# Power_VCC1V5.net
KiCad netlist of a schematic drawn in Altium Designer
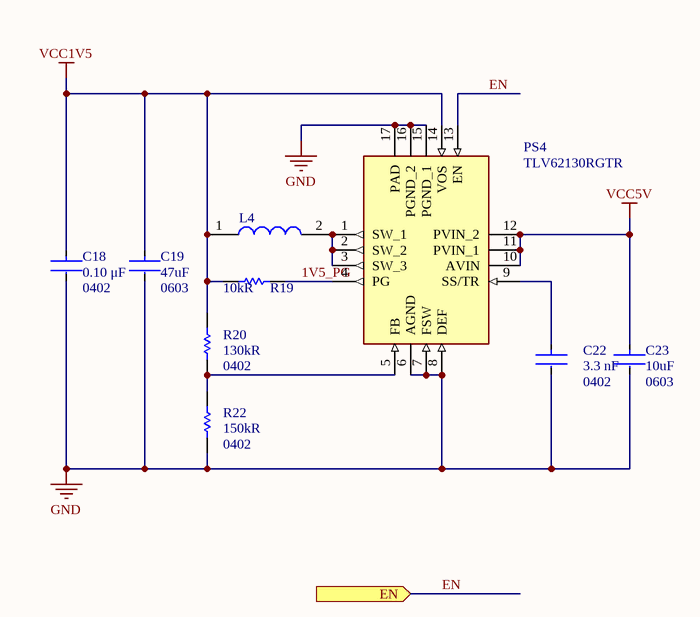
[diagram p0: Power_VCC1V5.SchDoc]

(export (version "E")
  (design (tool "Eeschema 10.0.6"))
  (components
    (comp (ref "C18")
      (value "0.10 μF")
      (footprint "FP-C0402-BB-MFG")
      (description "CAP CER 0.1UF 10V X5R 0402")
      (fields
        (field (name "MANUFACTURER") "Kemet")
        (field (name "TOLERANCE") "0.1")
        (field (name "CASE/PACKAGE") "0402")
      )
      (libsource (lib "Altium Content Vault") (part "b4654b650e69147ec39a6b967a45e02"))
    )
    (comp (ref "C19")
      (value "47uF")
      (footprint "FP-GRM188-0_2-IPC_B")
      (description "Chip Multilayer Ceramic Capacitors for General Purpose, 0603, 47uF, X5R, 15%, 20%, 6.3V")
      (fields
        (field (name "CASE CODE (IMPERIAL)") "0603")
        (field (name "TOLERANCE") "20%")
        (field (name "MANUFACTURER") "Murata")
      )
      (libsource (lib "Altium Content Vault") (part "11868f565c42a9108669ba33697ecf6"))
    )
    (comp (ref "C22")
      (value "3.3 nF")
      (footprint "FP-CC0402-MFG")
      (description "CAP CER 3300PF 50V X7R 0402")
      (fields
        (field (name "OCTOPART") "https://octopart.com/cc0402krx7r9bb332-yageo-192887")
        (field (name "MANUFACTURER") "YAGEO")
        (field (name "CASE/PACKAGE") "0402")
      )
      (libsource (lib "Altium Content Vault") (part "11868f565c42a9108669ba33697ecf6"))
    )
    (comp (ref "C23")
      (value "10uF")
      (footprint "FP-GRM188-0_1-e0_2_0_55-IPC_A")
      (description "Chip Multilayer Ceramic Capacitors for General Purpose, 0603, 10uF, X5R, 15%, 20%, 6.3V")
      (fields
        (field (name "CASE/PACKAGE") "0603")
        (field (name "VOLTAGE") "6.3V")
        (field (name "TOLERANCE") "20%")
      )
      (libsource (lib "Altium Content Vault") (part "02cd4be3c70576c341d710602a673aa"))
    )
    (comp (ref "L4")
      (value "252012CDMCDS2R2MC")
      (footprint "INDPM2520X120N")
      (description "Inductor")
      (fields (field (name "MANUFACTURER_PART_NUMBER") "252012CDMCDS‐2R2MC"))
      (libsource (lib "CCZynq") (part "252012CDMCDS2R2MC"))
    )
    (comp (ref "PS4")
      (value "TLV62130RGTR")
      (footprint "FP-RGT0016C-MFG")
      (description "Buck Switching Regulator IC Positive Adjustable 0.9V 1 Output 3A 16-VFQFN Exposed Pad")
      (fields
        (field (name "MOUSER PART NUMBER") "595-TLV62130RGTR")
        (field (name "MANUFACTURER") "Texas Instruments")
      )
      (libsource (lib "HamedLib") (part "TLV62130RGTR"))
    )
    (comp (ref "R19")
      (value "10kR")
      (footprint "RESC1005X40X25LL05T10")
      (description "10K 0402 1% 1/16W +-100PPM")
      (fields (field (name "PART NUMBER") "RC0402FR-0710KL") (field (name "MANUFACTURER") "Yageo / Phycomp"))
      (libsource (lib "Altium Content Vault") (part "RES"))
    )
    (comp (ref "R20")
      (value "130kR")
      (footprint "RESC1005X40X25NL05T05")
      (fields
        (field (name "MANUFACTURER") "Panasonic")
        (field (name "PART NUMBER") "ERJ-2GEJ134X")
        (field (name "CASE/PACKAGE") "0402")
        (field (name "TOLERANCE") "5%")
      )
      (libsource (lib "Altium Content Vault") (part "RES"))
    )
    (comp (ref "R22")
      (value "150kR")
      (footprint "RESC1005X40X25NL05T05")
      (fields
        (field (name "MANUFACTURER") "Vishay Dale")
        (field (name "PART NUMBER") "CRCW0402150KFKED")
        (field (name "CASE/PACKAGE") "0402")
        (field (name "TOLERANCE") "1%")
      )
      (libsource (lib "Altium Content Vault") (part "RES"))
    )
  )
  (nets
    (net (code "1") (name "/1V5_PG") (class "Default")
      (node (ref "PS4") (pin "4") (pinfunction "PG_4") (pintype "output"))
      (node (ref "R19") (pin "2") (pinfunction "2_2") (pintype "passive"))
    )
    (net (code "2") (name "/EN") (class "Default")
      (node (ref "PS4") (pin "13") (pinfunction "EN_13") (pintype "input"))
    )
    (net (code "3") (name "GND") (class "Default")
      (node (ref "C18") (pin "2") (pinfunction "2_2") (pintype "passive"))
      (node (ref "C19") (pin "2") (pinfunction "2_2") (pintype "passive"))
      (node (ref "C22") (pin "2") (pinfunction "2_2") (pintype "passive"))
      (node (ref "C23") (pin "2") (pinfunction "2_2") (pintype "passive"))
      (node (ref "PS4") (pin "15") (pinfunction "PGND_1_15") (pintype "power_in"))
      (node (ref "PS4") (pin "16") (pinfunction "PGND_2_16") (pintype "power_in"))
      (node (ref "PS4") (pin "17") (pinfunction "PAD_17") (pintype "power_in"))
      (node (ref "PS4") (pin "6") (pinfunction "AGND_6") (pintype "power_in"))
      (node (ref "PS4") (pin "7") (pinfunction "FSW_7") (pintype "input"))
      (node (ref "PS4") (pin "8") (pinfunction "DEF_8") (pintype "input"))
      (node (ref "R22") (pin "1") (pinfunction "1_1") (pintype "passive"))
    )
    (net (code "4") (name "Net-(PS4-FB)") (class "Default")
      (node (ref "PS4") (pin "5") (pinfunction "FB_5") (pintype "input"))
      (node (ref "R20") (pin "1") (pinfunction "1_1") (pintype "passive"))
      (node (ref "R22") (pin "2") (pinfunction "2_2") (pintype "passive"))
    )
    (net (code "5") (name "Net-(PS4-SS{slash}TR)") (class "Default")
      (node (ref "C22") (pin "1") (pinfunction "1_1") (pintype "passive"))
      (node (ref "PS4") (pin "9") (pinfunction "SS/TR_9") (pintype "input"))
    )
    (net (code "6") (name "Net-(PS4-SW_1)") (class "Default")
      (node (ref "L4") (pin "2") (pinfunction "2_2") (pintype "passive"))
      (node (ref "PS4") (pin "1") (pinfunction "SW_1_1") (pintype "output"))
      (node (ref "PS4") (pin "2") (pinfunction "SW_2_2") (pintype "output"))
      (node (ref "PS4") (pin "3") (pinfunction "SW_3_3") (pintype "output"))
    )
    (net (code "7") (name "VCC1V5") (class "Default")
      (node (ref "C18") (pin "1") (pinfunction "1_1") (pintype "passive"))
      (node (ref "C19") (pin "1") (pinfunction "1_1") (pintype "passive"))
      (node (ref "L4") (pin "1") (pinfunction "1_1") (pintype "passive"))
      (node (ref "PS4") (pin "14") (pinfunction "VOS_14") (pintype "input"))
      (node (ref "R19") (pin "1") (pinfunction "1_1") (pintype "passive"))
      (node (ref "R20") (pin "2") (pinfunction "2_2") (pintype "passive"))
    )
    (net (code "8") (name "VCC5V") (class "Default")
      (node (ref "C23") (pin "1") (pinfunction "1_1") (pintype "passive"))
      (node (ref "PS4") (pin "10") (pinfunction "AVIN_10") (pintype "power_in"))
      (node (ref "PS4") (pin "11") (pinfunction "PVIN_1_11") (pintype "power_in"))
      (node (ref "PS4") (pin "12") (pinfunction "PVIN_2_12") (pintype "power_in"))
    )
  )
)
